# OSIVE_Slim.net
KiCad netlist of a schematic drawn in EAGLE
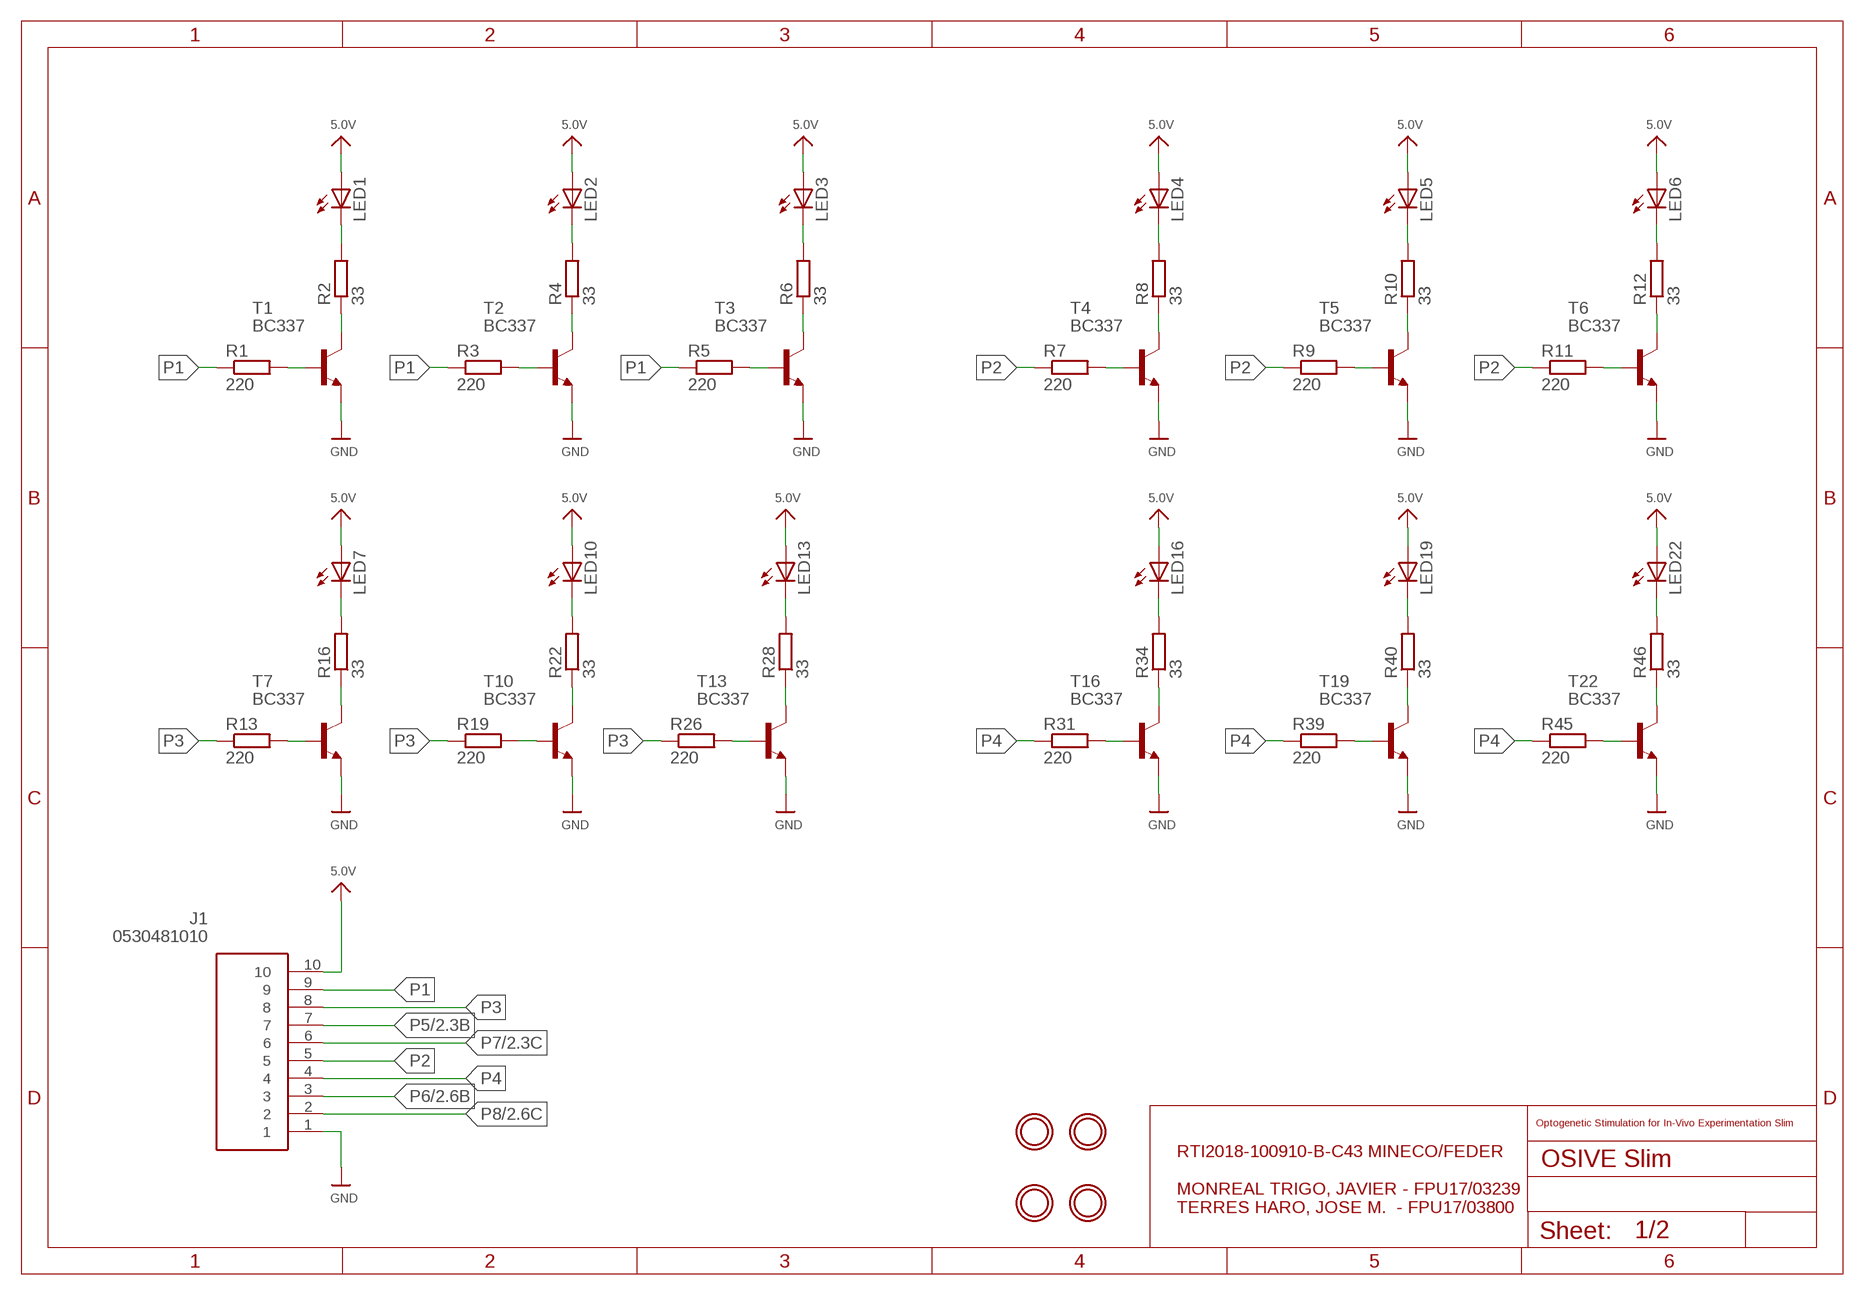
[diagram p0: schematic, sheet 1]
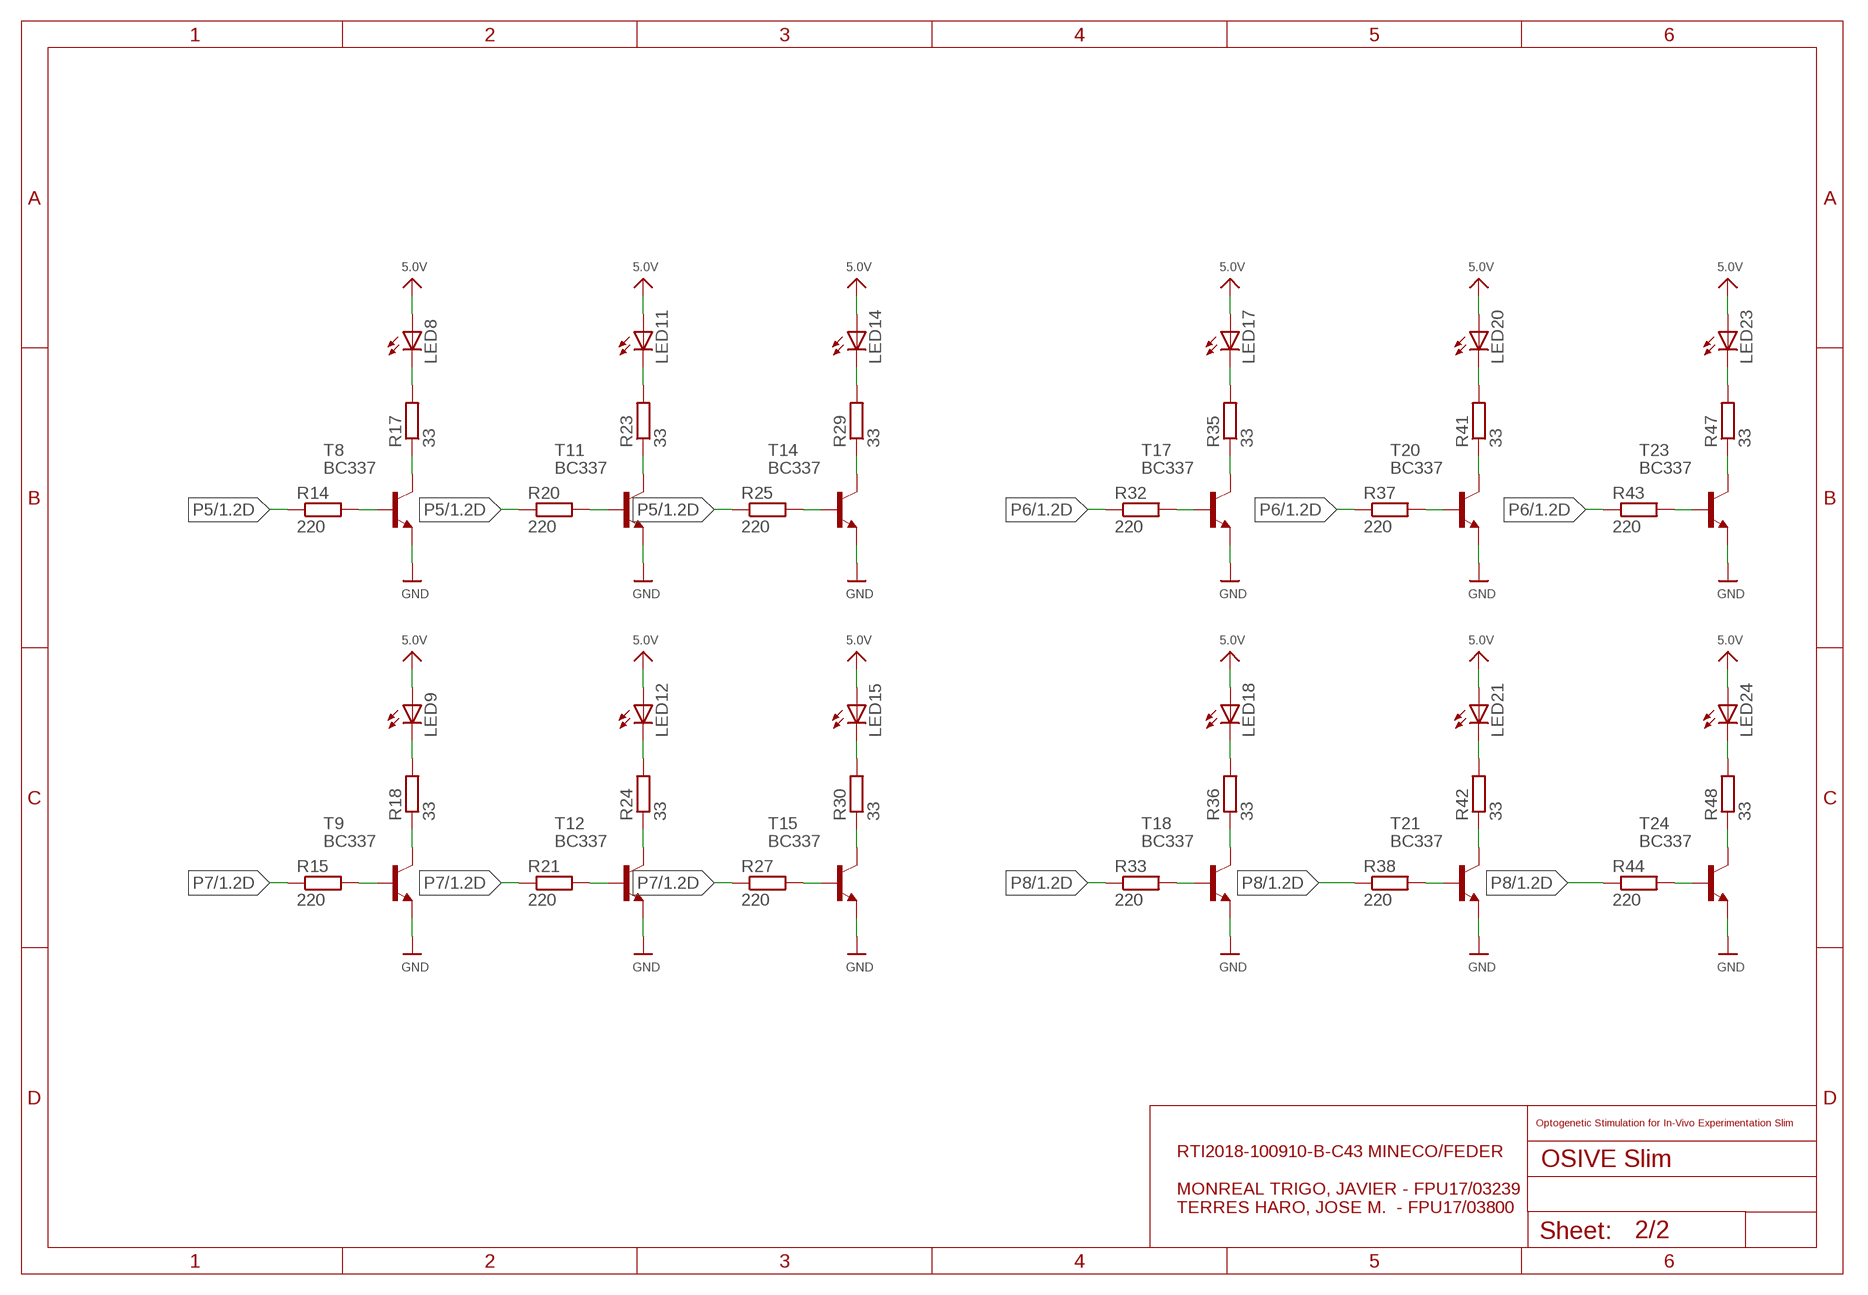
[diagram p1: schematic, sheet 2]

(export (version "E")
  (design (tool "Eeschema 10.0.6"))
  (components
    (comp (ref "LED8")
      (value "LED5MM")
      (footprint "eagle-import:LED5MM")
      (libsource (lib "eagle-import") (part "LED5MM"))
    )
    (comp (ref "LED9")
      (value "LED5MM")
      (footprint "eagle-import:LED5MM")
      (libsource (lib "eagle-import") (part "LED5MM"))
    )
    (comp (ref "LED11")
      (value "LED5MM")
      (footprint "eagle-import:LED5MM")
      (libsource (lib "eagle-import") (part "LED5MM"))
    )
    (comp (ref "LED12")
      (value "LED5MM")
      (footprint "eagle-import:LED5MM")
      (libsource (lib "eagle-import") (part "LED5MM"))
    )
    (comp (ref "LED14")
      (value "LED5MM")
      (footprint "eagle-import:LED5MM")
      (libsource (lib "eagle-import") (part "LED5MM"))
    )
    (comp (ref "LED15")
      (value "LED5MM")
      (footprint "eagle-import:LED5MM")
      (libsource (lib "eagle-import") (part "LED5MM"))
    )
    (comp (ref "LED17")
      (value "LED5MM")
      (footprint "eagle-import:LED5MM")
      (libsource (lib "eagle-import") (part "LED5MM"))
    )
    (comp (ref "LED18")
      (value "LED5MM")
      (footprint "eagle-import:LED5MM")
      (libsource (lib "eagle-import") (part "LED5MM"))
    )
    (comp (ref "LED20")
      (value "LED5MM")
      (footprint "eagle-import:LED5MM")
      (libsource (lib "eagle-import") (part "LED5MM"))
    )
    (comp (ref "LED21")
      (value "LED5MM")
      (footprint "eagle-import:LED5MM")
      (libsource (lib "eagle-import") (part "LED5MM"))
    )
    (comp (ref "LED23")
      (value "LED5MM")
      (footprint "eagle-import:LED5MM")
      (libsource (lib "eagle-import") (part "LED5MM"))
    )
    (comp (ref "LED24")
      (value "LED5MM")
      (footprint "eagle-import:LED5MM")
      (libsource (lib "eagle-import") (part "LED5MM"))
    )
    (comp (ref "R14")
      (value "220")
      (footprint "eagle-import:0204_7")
      (libsource (lib "eagle-import") (part "R-EU_0204/7"))
    )
    (comp (ref "R15")
      (value "220")
      (footprint "eagle-import:0204_7")
      (libsource (lib "eagle-import") (part "R-EU_0204/7"))
    )
    (comp (ref "R17")
      (value "33")
      (footprint "eagle-import:0204_7")
      (libsource (lib "eagle-import") (part "R-EU_0204/7"))
    )
    (comp (ref "R18")
      (value "33")
      (footprint "eagle-import:0204_7")
      (libsource (lib "eagle-import") (part "R-EU_0204/7"))
    )
    (comp (ref "R20")
      (value "220")
      (footprint "eagle-import:0204_7")
      (libsource (lib "eagle-import") (part "R-EU_0204/7"))
    )
    (comp (ref "R21")
      (value "220")
      (footprint "eagle-import:0204_7")
      (libsource (lib "eagle-import") (part "R-EU_0204/7"))
    )
    (comp (ref "R23")
      (value "33")
      (footprint "eagle-import:0204_7")
      (libsource (lib "eagle-import") (part "R-EU_0204/7"))
    )
    (comp (ref "R24")
      (value "33")
      (footprint "eagle-import:0204_7")
      (libsource (lib "eagle-import") (part "R-EU_0204/7"))
    )
    (comp (ref "R25")
      (value "220")
      (footprint "eagle-import:0204_7")
      (libsource (lib "eagle-import") (part "R-EU_0204/7"))
    )
    (comp (ref "R27")
      (value "220")
      (footprint "eagle-import:0204_7")
      (libsource (lib "eagle-import") (part "R-EU_0204/7"))
    )
    (comp (ref "R29")
      (value "33")
      (footprint "eagle-import:0204_7")
      (libsource (lib "eagle-import") (part "R-EU_0204/7"))
    )
    (comp (ref "R30")
      (value "33")
      (footprint "eagle-import:0204_7")
      (libsource (lib "eagle-import") (part "R-EU_0204/7"))
    )
    (comp (ref "R32")
      (value "220")
      (footprint "eagle-import:0204_7")
      (libsource (lib "eagle-import") (part "R-EU_0204/7"))
    )
    (comp (ref "R33")
      (value "220")
      (footprint "eagle-import:0204_7")
      (libsource (lib "eagle-import") (part "R-EU_0204/7"))
    )
    (comp (ref "R35")
      (value "33")
      (footprint "eagle-import:0204_7")
      (libsource (lib "eagle-import") (part "R-EU_0204/7"))
    )
    (comp (ref "R36")
      (value "33")
      (footprint "eagle-import:0204_7")
      (libsource (lib "eagle-import") (part "R-EU_0204/7"))
    )
    (comp (ref "R37")
      (value "220")
      (footprint "eagle-import:0204_7")
      (libsource (lib "eagle-import") (part "R-EU_0204/7"))
    )
    (comp (ref "R38")
      (value "220")
      (footprint "eagle-import:0204_7")
      (libsource (lib "eagle-import") (part "R-EU_0204/7"))
    )
    (comp (ref "R41")
      (value "33")
      (footprint "eagle-import:0204_7")
      (libsource (lib "eagle-import") (part "R-EU_0204/7"))
    )
    (comp (ref "R42")
      (value "33")
      (footprint "eagle-import:0204_7")
      (libsource (lib "eagle-import") (part "R-EU_0204/7"))
    )
    (comp (ref "R43")
      (value "220")
      (footprint "eagle-import:0204_7")
      (libsource (lib "eagle-import") (part "R-EU_0204/7"))
    )
    (comp (ref "R44")
      (value "220")
      (footprint "eagle-import:0204_7")
      (libsource (lib "eagle-import") (part "R-EU_0204/7"))
    )
    (comp (ref "R47")
      (value "33")
      (footprint "eagle-import:0204_7")
      (libsource (lib "eagle-import") (part "R-EU_0204/7"))
    )
    (comp (ref "R48")
      (value "33")
      (footprint "eagle-import:0204_7")
      (libsource (lib "eagle-import") (part "R-EU_0204/7"))
    )
    (comp (ref "T8")
      (value "BC337")
      (footprint "eagle-import:TO92")
      (libsource (lib "eagle-import") (part "BC337"))
    )
    (comp (ref "T9")
      (value "BC337")
      (footprint "eagle-import:TO92")
      (libsource (lib "eagle-import") (part "BC337"))
    )
    (comp (ref "T11")
      (value "BC337")
      (footprint "eagle-import:TO92")
      (libsource (lib "eagle-import") (part "BC337"))
    )
    (comp (ref "T12")
      (value "BC337")
      (footprint "eagle-import:TO92")
      (libsource (lib "eagle-import") (part "BC337"))
    )
    (comp (ref "T14")
      (value "BC337")
      (footprint "eagle-import:TO92")
      (libsource (lib "eagle-import") (part "BC337"))
    )
    (comp (ref "T15")
      (value "BC337")
      (footprint "eagle-import:TO92")
      (libsource (lib "eagle-import") (part "BC337"))
    )
    (comp (ref "T17")
      (value "BC337")
      (footprint "eagle-import:TO92")
      (libsource (lib "eagle-import") (part "BC337"))
    )
    (comp (ref "T18")
      (value "BC337")
      (footprint "eagle-import:TO92")
      (libsource (lib "eagle-import") (part "BC337"))
    )
    (comp (ref "T20")
      (value "BC337")
      (footprint "eagle-import:TO92")
      (libsource (lib "eagle-import") (part "BC337"))
    )
    (comp (ref "T21")
      (value "BC337")
      (footprint "eagle-import:TO92")
      (libsource (lib "eagle-import") (part "BC337"))
    )
    (comp (ref "T23")
      (value "BC337")
      (footprint "eagle-import:TO92")
      (libsource (lib "eagle-import") (part "BC337"))
    )
    (comp (ref "T24")
      (value "BC337")
      (footprint "eagle-import:TO92")
      (libsource (lib "eagle-import") (part "BC337"))
    )
    (comp (ref "H1")
      (value "MOUNTINGHOLE3.0THIN")
      (footprint "eagle-import:MOUNTINGHOLE_3.0_PLATEDTHIN")
      (libsource (lib "eagle-import") (part "MOUNTINGHOLE3.0THIN"))
    )
    (comp (ref "H2")
      (value "MOUNTINGHOLE3.0THIN")
      (footprint "eagle-import:MOUNTINGHOLE_3.0_PLATEDTHIN")
      (libsource (lib "eagle-import") (part "MOUNTINGHOLE3.0THIN"))
    )
    (comp (ref "H3")
      (value "MOUNTINGHOLE3.0THIN")
      (footprint "eagle-import:MOUNTINGHOLE_3.0_PLATEDTHIN")
      (libsource (lib "eagle-import") (part "MOUNTINGHOLE3.0THIN"))
    )
    (comp (ref "H4")
      (value "MOUNTINGHOLE3.0THIN")
      (footprint "eagle-import:MOUNTINGHOLE_3.0_PLATEDTHIN")
      (libsource (lib "eagle-import") (part "MOUNTINGHOLE3.0THIN"))
    )
    (comp (ref "J1")
      (value "0530481010")
      (footprint "eagle-import:0530481010")
      (libsource (lib "eagle-import") (part "0530481010"))
    )
    (comp (ref "LED1")
      (value "LED5MM")
      (footprint "eagle-import:LED5MM")
      (libsource (lib "eagle-import") (part "LED5MM"))
    )
    (comp (ref "LED2")
      (value "LED5MM")
      (footprint "eagle-import:LED5MM")
      (libsource (lib "eagle-import") (part "LED5MM"))
    )
    (comp (ref "LED3")
      (value "LED5MM")
      (footprint "eagle-import:LED5MM")
      (libsource (lib "eagle-import") (part "LED5MM"))
    )
    (comp (ref "LED4")
      (value "LED5MM")
      (footprint "eagle-import:LED5MM")
      (libsource (lib "eagle-import") (part "LED5MM"))
    )
    (comp (ref "LED5")
      (value "LED5MM")
      (footprint "eagle-import:LED5MM")
      (libsource (lib "eagle-import") (part "LED5MM"))
    )
    (comp (ref "LED6")
      (value "LED5MM")
      (footprint "eagle-import:LED5MM")
      (libsource (lib "eagle-import") (part "LED5MM"))
    )
    (comp (ref "LED7")
      (value "LED5MM")
      (footprint "eagle-import:LED5MM")
      (libsource (lib "eagle-import") (part "LED5MM"))
    )
    (comp (ref "LED10")
      (value "LED5MM")
      (footprint "eagle-import:LED5MM")
      (libsource (lib "eagle-import") (part "LED5MM"))
    )
    (comp (ref "LED13")
      (value "LED5MM")
      (footprint "eagle-import:LED5MM")
      (libsource (lib "eagle-import") (part "LED5MM"))
    )
    (comp (ref "LED16")
      (value "LED5MM")
      (footprint "eagle-import:LED5MM")
      (libsource (lib "eagle-import") (part "LED5MM"))
    )
    (comp (ref "LED19")
      (value "LED5MM")
      (footprint "eagle-import:LED5MM")
      (libsource (lib "eagle-import") (part "LED5MM"))
    )
    (comp (ref "LED22")
      (value "LED5MM")
      (footprint "eagle-import:LED5MM")
      (libsource (lib "eagle-import") (part "LED5MM"))
    )
    (comp (ref "R1")
      (value "220")
      (footprint "eagle-import:0204_7")
      (libsource (lib "eagle-import") (part "R-EU_0204/7"))
    )
    (comp (ref "R2")
      (value "33")
      (footprint "eagle-import:0204_7")
      (libsource (lib "eagle-import") (part "R-EU_0204/7"))
    )
    (comp (ref "R3")
      (value "220")
      (footprint "eagle-import:0204_7")
      (libsource (lib "eagle-import") (part "R-EU_0204/7"))
    )
    (comp (ref "R4")
      (value "33")
      (footprint "eagle-import:0204_7")
      (libsource (lib "eagle-import") (part "R-EU_0204/7"))
    )
    (comp (ref "R5")
      (value "220")
      (footprint "eagle-import:0204_7")
      (libsource (lib "eagle-import") (part "R-EU_0204/7"))
    )
    (comp (ref "R6")
      (value "33")
      (footprint "eagle-import:0204_7")
      (libsource (lib "eagle-import") (part "R-EU_0204/7"))
    )
    (comp (ref "R7")
      (value "220")
      (footprint "eagle-import:0204_7")
      (libsource (lib "eagle-import") (part "R-EU_0204/7"))
    )
    (comp (ref "R8")
      (value "33")
      (footprint "eagle-import:0204_7")
      (libsource (lib "eagle-import") (part "R-EU_0204/7"))
    )
    (comp (ref "R9")
      (value "220")
      (footprint "eagle-import:0204_7")
      (libsource (lib "eagle-import") (part "R-EU_0204/7"))
    )
    (comp (ref "R10")
      (value "33")
      (footprint "eagle-import:0204_7")
      (libsource (lib "eagle-import") (part "R-EU_0204/7"))
    )
    (comp (ref "R11")
      (value "220")
      (footprint "eagle-import:0204_7")
      (libsource (lib "eagle-import") (part "R-EU_0204/7"))
    )
    (comp (ref "R12")
      (value "33")
      (footprint "eagle-import:0204_7")
      (libsource (lib "eagle-import") (part "R-EU_0204/7"))
    )
    (comp (ref "R13")
      (value "220")
      (footprint "eagle-import:0204_7")
      (libsource (lib "eagle-import") (part "R-EU_0204/7"))
    )
    (comp (ref "R16")
      (value "33")
      (footprint "eagle-import:0204_7")
      (libsource (lib "eagle-import") (part "R-EU_0204/7"))
    )
    (comp (ref "R19")
      (value "220")
      (footprint "eagle-import:0204_7")
      (libsource (lib "eagle-import") (part "R-EU_0204/7"))
    )
    (comp (ref "R22")
      (value "33")
      (footprint "eagle-import:0204_7")
      (libsource (lib "eagle-import") (part "R-EU_0204/7"))
    )
    (comp (ref "R26")
      (value "220")
      (footprint "eagle-import:0204_7")
      (libsource (lib "eagle-import") (part "R-EU_0204/7"))
    )
    (comp (ref "R28")
      (value "33")
      (footprint "eagle-import:0204_7")
      (libsource (lib "eagle-import") (part "R-EU_0204/7"))
    )
    (comp (ref "R31")
      (value "220")
      (footprint "eagle-import:0204_7")
      (libsource (lib "eagle-import") (part "R-EU_0204/7"))
    )
    (comp (ref "R34")
      (value "33")
      (footprint "eagle-import:0204_7")
      (libsource (lib "eagle-import") (part "R-EU_0204/7"))
    )
    (comp (ref "R39")
      (value "220")
      (footprint "eagle-import:0204_7")
      (libsource (lib "eagle-import") (part "R-EU_0204/7"))
    )
    (comp (ref "R40")
      (value "33")
      (footprint "eagle-import:0204_7")
      (libsource (lib "eagle-import") (part "R-EU_0204/7"))
    )
    (comp (ref "R45")
      (value "220")
      (footprint "eagle-import:0204_7")
      (libsource (lib "eagle-import") (part "R-EU_0204/7"))
    )
    (comp (ref "R46")
      (value "33")
      (footprint "eagle-import:0204_7")
      (libsource (lib "eagle-import") (part "R-EU_0204/7"))
    )
    (comp (ref "T1")
      (value "BC337")
      (footprint "eagle-import:TO92")
      (libsource (lib "eagle-import") (part "BC337"))
    )
    (comp (ref "T2")
      (value "BC337")
      (footprint "eagle-import:TO92")
      (libsource (lib "eagle-import") (part "BC337"))
    )
    (comp (ref "T3")
      (value "BC337")
      (footprint "eagle-import:TO92")
      (libsource (lib "eagle-import") (part "BC337"))
    )
    (comp (ref "T4")
      (value "BC337")
      (footprint "eagle-import:TO92")
      (libsource (lib "eagle-import") (part "BC337"))
    )
    (comp (ref "T5")
      (value "BC337")
      (footprint "eagle-import:TO92")
      (libsource (lib "eagle-import") (part "BC337"))
    )
    (comp (ref "T6")
      (value "BC337")
      (footprint "eagle-import:TO92")
      (libsource (lib "eagle-import") (part "BC337"))
    )
    (comp (ref "T7")
      (value "BC337")
      (footprint "eagle-import:TO92")
      (libsource (lib "eagle-import") (part "BC337"))
    )
    (comp (ref "T10")
      (value "BC337")
      (footprint "eagle-import:TO92")
      (libsource (lib "eagle-import") (part "BC337"))
    )
    (comp (ref "T13")
      (value "BC337")
      (footprint "eagle-import:TO92")
      (libsource (lib "eagle-import") (part "BC337"))
    )
    (comp (ref "T16")
      (value "BC337")
      (footprint "eagle-import:TO92")
      (libsource (lib "eagle-import") (part "BC337"))
    )
    (comp (ref "T19")
      (value "BC337")
      (footprint "eagle-import:TO92")
      (libsource (lib "eagle-import") (part "BC337"))
    )
    (comp (ref "T22")
      (value "BC337")
      (footprint "eagle-import:TO92")
      (libsource (lib "eagle-import") (part "BC337"))
    )
  )
  (nets
    (net (code "1") (name "5.0V") (class "Default")
      (node (ref "J1") (pin "10") (pinfunction "10_10") (pintype "bidirectional"))
      (node (ref "LED1") (pin "A") (pinfunction "A_A") (pintype "passive"))
      (node (ref "LED10") (pin "A") (pinfunction "A_A") (pintype "passive"))
      (node (ref "LED11") (pin "A") (pinfunction "A_A") (pintype "passive"))
      (node (ref "LED12") (pin "A") (pinfunction "A_A") (pintype "passive"))
      (node (ref "LED13") (pin "A") (pinfunction "A_A") (pintype "passive"))
      (node (ref "LED14") (pin "A") (pinfunction "A_A") (pintype "passive"))
      (node (ref "LED15") (pin "A") (pinfunction "A_A") (pintype "passive"))
      (node (ref "LED16") (pin "A") (pinfunction "A_A") (pintype "passive"))
      (node (ref "LED17") (pin "A") (pinfunction "A_A") (pintype "passive"))
      (node (ref "LED18") (pin "A") (pinfunction "A_A") (pintype "passive"))
      (node (ref "LED19") (pin "A") (pinfunction "A_A") (pintype "passive"))
      (node (ref "LED2") (pin "A") (pinfunction "A_A") (pintype "passive"))
      (node (ref "LED20") (pin "A") (pinfunction "A_A") (pintype "passive"))
      (node (ref "LED21") (pin "A") (pinfunction "A_A") (pintype "passive"))
      (node (ref "LED22") (pin "A") (pinfunction "A_A") (pintype "passive"))
      (node (ref "LED23") (pin "A") (pinfunction "A_A") (pintype "passive"))
      (node (ref "LED24") (pin "A") (pinfunction "A_A") (pintype "passive"))
      (node (ref "LED3") (pin "A") (pinfunction "A_A") (pintype "passive"))
      (node (ref "LED4") (pin "A") (pinfunction "A_A") (pintype "passive"))
      (node (ref "LED5") (pin "A") (pinfunction "A_A") (pintype "passive"))
      (node (ref "LED6") (pin "A") (pinfunction "A_A") (pintype "passive"))
      (node (ref "LED7") (pin "A") (pinfunction "A_A") (pintype "passive"))
      (node (ref "LED8") (pin "A") (pinfunction "A_A") (pintype "passive"))
      (node (ref "LED9") (pin "A") (pinfunction "A_A") (pintype "passive"))
    )
    (net (code "2") (name "GND") (class "Default")
      (node (ref "J1") (pin "1") (pinfunction "1_1") (pintype "bidirectional"))
      (node (ref "T1") (pin "1") (pinfunction "E_1") (pintype "passive"))
      (node (ref "T10") (pin "1") (pinfunction "E_1") (pintype "passive"))
      (node (ref "T11") (pin "1") (pinfunction "E_1") (pintype "passive"))
      (node (ref "T12") (pin "1") (pinfunction "E_1") (pintype "passive"))
      (node (ref "T13") (pin "1") (pinfunction "E_1") (pintype "passive"))
      (node (ref "T14") (pin "1") (pinfunction "E_1") (pintype "passive"))
      (node (ref "T15") (pin "1") (pinfunction "E_1") (pintype "passive"))
      (node (ref "T16") (pin "1") (pinfunction "E_1") (pintype "passive"))
      (node (ref "T17") (pin "1") (pinfunction "E_1") (pintype "passive"))
      (node (ref "T18") (pin "1") (pinfunction "E_1") (pintype "passive"))
      (node (ref "T19") (pin "1") (pinfunction "E_1") (pintype "passive"))
      (node (ref "T2") (pin "1") (pinfunction "E_1") (pintype "passive"))
      (node (ref "T20") (pin "1") (pinfunction "E_1") (pintype "passive"))
      (node (ref "T21") (pin "1") (pinfunction "E_1") (pintype "passive"))
      (node (ref "T22") (pin "1") (pinfunction "E_1") (pintype "passive"))
      (node (ref "T23") (pin "1") (pinfunction "E_1") (pintype "passive"))
      (node (ref "T24") (pin "1") (pinfunction "E_1") (pintype "passive"))
      (node (ref "T3") (pin "1") (pinfunction "E_1") (pintype "passive"))
      (node (ref "T4") (pin "1") (pinfunction "E_1") (pintype "passive"))
      (node (ref "T5") (pin "1") (pinfunction "E_1") (pintype "passive"))
      (node (ref "T6") (pin "1") (pinfunction "E_1") (pintype "passive"))
      (node (ref "T7") (pin "1") (pinfunction "E_1") (pintype "passive"))
      (node (ref "T8") (pin "1") (pinfunction "E_1") (pintype "passive"))
      (node (ref "T9") (pin "1") (pinfunction "E_1") (pintype "passive"))
    )
    (net (code "3") (name "Net-(LED1-C)") (class "Default")
      (node (ref "LED1") (pin "K") (pinfunction "C_K") (pintype "passive"))
      (node (ref "R2") (pin "2") (pinfunction "2_2") (pintype "passive"))
    )
    (net (code "4") (name "Net-(LED2-C)") (class "Default")
      (node (ref "LED2") (pin "K") (pinfunction "C_K") (pintype "passive"))
      (node (ref "R4") (pin "2") (pinfunction "2_2") (pintype "passive"))
    )
    (net (code "5") (name "Net-(LED3-C)") (class "Default")
      (node (ref "LED3") (pin "K") (pinfunction "C_K") (pintype "passive"))
      (node (ref "R6") (pin "2") (pinfunction "2_2") (pintype "passive"))
    )
    (net (code "6") (name "Net-(LED4-C)") (class "Default")
      (node (ref "LED4") (pin "K") (pinfunction "C_K") (pintype "passive"))
      (node (ref "R8") (pin "2") (pinfunction "2_2") (pintype "passive"))
    )
    (net (code "7") (name "Net-(LED5-C)") (class "Default")
      (node (ref "LED5") (pin "K") (pinfunction "C_K") (pintype "passive"))
      (node (ref "R10") (pin "2") (pinfunction "2_2") (pintype "passive"))
    )
    (net (code "8") (name "Net-(LED6-C)") (class "Default")
      (node (ref "LED6") (pin "K") (pinfunction "C_K") (pintype "passive"))
      (node (ref "R12") (pin "2") (pinfunction "2_2") (pintype "passive"))
    )
    (net (code "9") (name "Net-(LED7-C)") (class "Default")
      (node (ref "LED7") (pin "K") (pinfunction "C_K") (pintype "passive"))
      (node (ref "R16") (pin "2") (pinfunction "2_2") (pintype "passive"))
    )
    (net (code "10") (name "Net-(LED8-C)") (class "Default")
      (node (ref "LED8") (pin "K") (pinfunction "C_K") (pintype "passive"))
      (node (ref "R17") (pin "2") (pinfunction "2_2") (pintype "passive"))
    )
    (net (code "11") (name "Net-(LED9-C)") (class "Default")
      (node (ref "LED9") (pin "K") (pinfunction "C_K") (pintype "passive"))
      (node (ref "R18") (pin "2") (pinfunction "2_2") (pintype "passive"))
    )
    (net (code "12") (name "Net-(LED10-C)") (class "Default")
      (node (ref "LED10") (pin "K") (pinfunction "C_K") (pintype "passive"))
      (node (ref "R22") (pin "2") (pinfunction "2_2") (pintype "passive"))
    )
    (net (code "13") (name "Net-(LED11-C)") (class "Default")
      (node (ref "LED11") (pin "K") (pinfunction "C_K") (pintype "passive"))
      (node (ref "R23") (pin "2") (pinfunction "2_2") (pintype "passive"))
    )
    (net (code "14") (name "Net-(LED12-C)") (class "Default")
      (node (ref "LED12") (pin "K") (pinfunction "C_K") (pintype "passive"))
      (node (ref "R24") (pin "2") (pinfunction "2_2") (pintype "passive"))
    )
    (net (code "15") (name "Net-(LED13-C)") (class "Default")
      (node (ref "LED13") (pin "K") (pinfunction "C_K") (pintype "passive"))
      (node (ref "R28") (pin "2") (pinfunction "2_2") (pintype "passive"))
    )
    (net (code "16") (name "Net-(LED14-C)") (class "Default")
      (node (ref "LED14") (pin "K") (pinfunction "C_K") (pintype "passive"))
      (node (ref "R29") (pin "2") (pinfunction "2_2") (pintype "passive"))
    )
    (net (code "17") (name "Net-(LED15-C)") (class "Default")
      (node (ref "LED15") (pin "K") (pinfunction "C_K") (pintype "passive"))
      (node (ref "R30") (pin "2") (pinfunction "2_2") (pintype "passive"))
    )
    (net (code "18") (name "Net-(LED16-C)") (class "Default")
      (node (ref "LED16") (pin "K") (pinfunction "C_K") (pintype "passive"))
      (node (ref "R34") (pin "2") (pinfunction "2_2") (pintype "passive"))
    )
    (net (code "19") (name "Net-(LED17-C)") (class "Default")
      (node (ref "LED17") (pin "K") (pinfunction "C_K") (pintype "passive"))
      (node (ref "R35") (pin "2") (pinfunction "2_2") (pintype "passive"))
    )
    (net (code "20") (name "Net-(LED18-C)") (class "Default")
      (node (ref "LED18") (pin "K") (pinfunction "C_K") (pintype "passive"))
      (node (ref "R36") (pin "2") (pinfunction "2_2") (pintype "passive"))
    )
    (net (code "21") (name "Net-(LED19-C)") (class "Default")
      (node (ref "LED19") (pin "K") (pinfunction "C_K") (pintype "passive"))
      (node (ref "R40") (pin "2") (pinfunction "2_2") (pintype "passive"))
    )
    (net (code "22") (name "Net-(LED20-C)") (class "Default")
      (node (ref "LED20") (pin "K") (pinfunction "C_K") (pintype "passive"))
      (node (ref "R41") (pin "2") (pinfunction "2_2") (pintype "passive"))
    )
    (net (code "23") (name "Net-(LED21-C)") (class "Default")
      (node (ref "LED21") (pin "K") (pinfunction "C_K") (pintype "passive"))
      (node (ref "R42") (pin "2") (pinfunction "2_2") (pintype "passive"))
    )
    (net (code "24") (name "Net-(LED22-C)") (class "Default")
      (node (ref "LED22") (pin "K") (pinfunction "C_K") (pintype "passive"))
      (node (ref "R46") (pin "2") (pinfunction "2_2") (pintype "passive"))
    )
    (net (code "25") (name "Net-(LED23-C)") (class "Default")
      (node (ref "LED23") (pin "K") (pinfunction "C_K") (pintype "passive"))
      (node (ref "R47") (pin "2") (pinfunction "2_2") (pintype "passive"))
    )
    (net (code "26") (name "Net-(LED24-C)") (class "Default")
      (node (ref "LED24") (pin "K") (pinfunction "C_K") (pintype "passive"))
      (node (ref "R48") (pin "2") (pinfunction "2_2") (pintype "passive"))
    )
    (net (code "27") (name "Net-(T1-B)") (class "Default")
      (node (ref "R1") (pin "2") (pinfunction "2_2") (pintype "passive"))
      (node (ref "T1") (pin "2") (pinfunction "B_2") (pintype "passive"))
    )
    (net (code "28") (name "Net-(T1-C)") (class "Default")
      (node (ref "R2") (pin "1") (pinfunction "1_1") (pintype "passive"))
      (node (ref "T1") (pin "3") (pinfunction "C_3") (pintype "passive"))
    )
    (net (code "29") (name "Net-(T2-B)") (class "Default")
      (node (ref "R3") (pin "2") (pinfunction "2_2") (pintype "passive"))
      (node (ref "T2") (pin "2") (pinfunction "B_2") (pintype "passive"))
    )
    (net (code "30") (name "Net-(T2-C)") (class "Default")
      (node (ref "R4") (pin "1") (pinfunction "1_1") (pintype "passive"))
      (node (ref "T2") (pin "3") (pinfunction "C_3") (pintype "passive"))
    )
    (net (code "31") (name "Net-(T3-B)") (class "Default")
      (node (ref "R5") (pin "2") (pinfunction "2_2") (pintype "passive"))
      (node (ref "T3") (pin "2") (pinfunction "B_2") (pintype "passive"))
    )
    (net (code "32") (name "Net-(T3-C)") (class "Default")
      (node (ref "R6") (pin "1") (pinfunction "1_1") (pintype "passive"))
      (node (ref "T3") (pin "3") (pinfunction "C_3") (pintype "passive"))
    )
    (net (code "33") (name "Net-(T4-B)") (class "Default")
      (node (ref "R7") (pin "2") (pinfunction "2_2") (pintype "passive"))
      (node (ref "T4") (pin "2") (pinfunction "B_2") (pintype "passive"))
    )
    (net (code "34") (name "Net-(T4-C)") (class "Default")
      (node (ref "R8") (pin "1") (pinfunction "1_1") (pintype "passive"))
      (node (ref "T4") (pin "3") (pinfunction "C_3") (pintype "passive"))
    )
    (net (code "35") (name "Net-(T5-B)") (class "Default")
      (node (ref "R9") (pin "2") (pinfunction "2_2") (pintype "passive"))
      (node (ref "T5") (pin "2") (pinfunction "B_2") (pintype "passive"))
    )
    (net (code "36") (name "Net-(T5-C)") (class "Default")
      (node (ref "R10") (pin "1") (pinfunction "1_1") (pintype "passive"))
      (node (ref "T5") (pin "3") (pinfunction "C_3") (pintype "passive"))
    )
    (net (code "37") (name "Net-(T6-B)") (class "Default")
      (node (ref "R11") (pin "2") (pinfunction "2_2") (pintype "passive"))
      (node (ref "T6") (pin "2") (pinfunction "B_2") (pintype "passive"))
    )
    (net (code "38") (name "Net-(T6-C)") (class "Default")
      (node (ref "R12") (pin "1") (pinfunction "1_1") (pintype "passive"))
      (node (ref "T6") (pin "3") (pinfunction "C_3") (pintype "passive"))
    )
    (net (code "39") (name "Net-(T7-B)") (class "Default")
      (node (ref "R13") (pin "2") (pinfunction "2_2") (pintype "passive"))
      (node (ref "T7") (pin "2") (pinfunction "B_2") (pintype "passive"))
    )
    (net (code "40") (name "Net-(T7-C)") (class "Default")
      (node (ref "R16") (pin "1") (pinfunction "1_1") (pintype "passive"))
      (node (ref "T7") (pin "3") (pinfunction "C_3") (pintype "passive"))
    )
    (net (code "41") (name "Net-(T8-B)") (class "Default")
      (node (ref "R14") (pin "2") (pinfunction "2_2") (pintype "passive"))
      (node (ref "T8") (pin "2") (pinfunction "B_2") (pintype "passive"))
    )
    (net (code "42") (name "Net-(T8-C)") (class "Default")
      (node (ref "R17") (pin "1") (pinfunction "1_1") (pintype "passive"))
      (node (ref "T8") (pin "3") (pinfunction "C_3") (pintype "passive"))
    )
    (net (code "43") (name "Net-(T9-B)") (class "Default")
      (node (ref "R15") (pin "2") (pinfunction "2_2") (pintype "passive"))
      (node (ref "T9") (pin "2") (pinfunction "B_2") (pintype "passive"))
    )
    (net (code "44") (name "Net-(T9-C)") (class "Default")
      (node (ref "R18") (pin "1") (pinfunction "1_1") (pintype "passive"))
      (node (ref "T9") (pin "3") (pinfunction "C_3") (pintype "passive"))
    )
    (net (code "45") (name "Net-(T10-B)") (class "Default")
      (node (ref "R19") (pin "2") (pinfunction "2_2") (pintype "passive"))
      (node (ref "T10") (pin "2") (pinfunction "B_2") (pintype "passive"))
    )
    (net (code "46") (name "Net-(T10-C)") (class "Default")
      (node (ref "R22") (pin "1") (pinfunction "1_1") (pintype "passive"))
      (node (ref "T10") (pin "3") (pinfunction "C_3") (pintype "passive"))
    )
    (net (code "47") (name "Net-(T11-B)") (class "Default")
      (node (ref "R20") (pin "2") (pinfunction "2_2") (pintype "passive"))
      (node (ref "T11") (pin "2") (pinfunction "B_2") (pintype "passive"))
    )
    (net (code "48") (name "Net-(T11-C)") (class "Default")
      (node (ref "R23") (pin "1") (pinfunction "1_1") (pintype "passive"))
      (node (ref "T11") (pin "3") (pinfunction "C_3") (pintype "passive"))
    )
    (net (code "49") (name "Net-(T12-B)") (class "Default")
      (node (ref "R21") (pin "2") (pinfunction "2_2") (pintype "passive"))
      (node (ref "T12") (pin "2") (pinfunction "B_2") (pintype "passive"))
    )
    (net (code "50") (name "Net-(T12-C)") (class "Default")
      (node (ref "R24") (pin "1") (pinfunction "1_1") (pintype "passive"))
      (node (ref "T12") (pin "3") (pinfunction "C_3") (pintype "passive"))
    )
    (net (code "51") (name "Net-(T13-B)") (class "Default")
      (node (ref "R26") (pin "2") (pinfunction "2_2") (pintype "passive"))
      (node (ref "T13") (pin "2") (pinfunction "B_2") (pintype "passive"))
    )
    (net (code "52") (name "Net-(T13-C)") (class "Default")
      (node (ref "R28") (pin "1") (pinfunction "1_1") (pintype "passive"))
      (node (ref "T13") (pin "3") (pinfunction "C_3") (pintype "passive"))
    )
    (net (code "53") (name "Net-(T14-B)") (class "Default")
      (node (ref "R25") (pin "2") (pinfunction "2_2") (pintype "passive"))
      (node (ref "T14") (pin "2") (pinfunction "B_2") (pintype "passive"))
    )
    (net (code "54") (name "Net-(T14-C)") (class "Default")
      (node (ref "R29") (pin "1") (pinfunction "1_1") (pintype "passive"))
      (node (ref "T14") (pin "3") (pinfunction "C_3") (pintype "passive"))
    )
    (net (code "55") (name "Net-(T15-B)") (class "Default")
      (node (ref "R27") (pin "2") (pinfunction "2_2") (pintype "passive"))
      (node (ref "T15") (pin "2") (pinfunction "B_2") (pintype "passive"))
    )
    (net (code "56") (name "Net-(T15-C)") (class "Default")
      (node (ref "R30") (pin "1") (pinfunction "1_1") (pintype "passive"))
      (node (ref "T15") (pin "3") (pinfunction "C_3") (pintype "passive"))
    )
    (net (code "57") (name "Net-(T16-B)") (class "Default")
      (node (ref "R31") (pin "2") (pinfunction "2_2") (pintype "passive"))
      (node (ref "T16") (pin "2") (pinfunction "B_2") (pintype "passive"))
    )
    (net (code "58") (name "Net-(T16-C)") (class "Default")
      (node (ref "R34") (pin "1") (pinfunction "1_1") (pintype "passive"))
      (node (ref "T16") (pin "3") (pinfunction "C_3") (pintype "passive"))
    )
    (net (code "59") (name "Net-(T17-B)") (class "Default")
      (node (ref "R32") (pin "2") (pinfunction "2_2") (pintype "passive"))
      (node (ref "T17") (pin "2") (pinfunction "B_2") (pintype "passive"))
    )
    (net (code "60") (name "Net-(T17-C)") (class "Default")
      (node (ref "R35") (pin "1") (pinfunction "1_1") (pintype "passive"))
      (node (ref "T17") (pin "3") (pinfunction "C_3") (pintype "passive"))
    )
    (net (code "61") (name "Net-(T18-B)") (class "Default")
      (node (ref "R33") (pin "2") (pinfunction "2_2") (pintype "passive"))
      (node (ref "T18") (pin "2") (pinfunction "B_2") (pintype "passive"))
    )
    (net (code "62") (name "Net-(T18-C)") (class "Default")
      (node (ref "R36") (pin "1") (pinfunction "1_1") (pintype "passive"))
      (node (ref "T18") (pin "3") (pinfunction "C_3") (pintype "passive"))
    )
    (net (code "63") (name "Net-(T19-B)") (class "Default")
      (node (ref "R39") (pin "2") (pinfunction "2_2") (pintype "passive"))
      (node (ref "T19") (pin "2") (pinfunction "B_2") (pintype "passive"))
    )
    (net (code "64") (name "Net-(T19-C)") (class "Default")
      (node (ref "R40") (pin "1") (pinfunction "1_1") (pintype "passive"))
      (node (ref "T19") (pin "3") (pinfunction "C_3") (pintype "passive"))
    )
    (net (code "65") (name "Net-(T20-B)") (class "Default")
      (node (ref "R37") (pin "2") (pinfunction "2_2") (pintype "passive"))
      (node (ref "T20") (pin "2") (pinfunction "B_2") (pintype "passive"))
    )
    (net (code "66") (name "Net-(T20-C)") (class "Default")
      (node (ref "R41") (pin "1") (pinfunction "1_1") (pintype "passive"))
      (node (ref "T20") (pin "3") (pinfunction "C_3") (pintype "passive"))
    )
    (net (code "67") (name "Net-(T21-B)") (class "Default")
      (node (ref "R38") (pin "2") (pinfunction "2_2") (pintype "passive"))
      (node (ref "T21") (pin "2") (pinfunction "B_2") (pintype "passive"))
    )
    (net (code "68") (name "Net-(T21-C)") (class "Default")
      (node (ref "R42") (pin "1") (pinfunction "1_1") (pintype "passive"))
      (node (ref "T21") (pin "3") (pinfunction "C_3") (pintype "passive"))
    )
    (net (code "69") (name "Net-(T22-B)") (class "Default")
      (node (ref "R45") (pin "2") (pinfunction "2_2") (pintype "passive"))
      (node (ref "T22") (pin "2") (pinfunction "B_2") (pintype "passive"))
    )
    (net (code "70") (name "Net-(T22-C)") (class "Default")
      (node (ref "R46") (pin "1") (pinfunction "1_1") (pintype "passive"))
      (node (ref "T22") (pin "3") (pinfunction "C_3") (pintype "passive"))
    )
    (net (code "71") (name "Net-(T23-B)") (class "Default")
      (node (ref "R43") (pin "2") (pinfunction "2_2") (pintype "passive"))
      (node (ref "T23") (pin "2") (pinfunction "B_2") (pintype "passive"))
    )
    (net (code "72") (name "Net-(T23-C)") (class "Default")
      (node (ref "R47") (pin "1") (pinfunction "1_1") (pintype "passive"))
      (node (ref "T23") (pin "3") (pinfunction "C_3") (pintype "passive"))
    )
    (net (code "73") (name "Net-(T24-B)") (class "Default")
      (node (ref "R44") (pin "2") (pinfunction "2_2") (pintype "passive"))
      (node (ref "T24") (pin "2") (pinfunction "B_2") (pintype "passive"))
    )
    (net (code "74") (name "Net-(T24-C)") (class "Default")
      (node (ref "R48") (pin "1") (pinfunction "1_1") (pintype "passive"))
      (node (ref "T24") (pin "3") (pinfunction "C_3") (pintype "passive"))
    )
    (net (code "75") (name "P1") (class "Default")
      (node (ref "J1") (pin "9") (pinfunction "9_9") (pintype "bidirectional"))
      (node (ref "R1") (pin "1") (pinfunction "1_1") (pintype "passive"))
      (node (ref "R3") (pin "1") (pinfunction "1_1") (pintype "passive"))
      (node (ref "R5") (pin "1") (pinfunction "1_1") (pintype "passive"))
    )
    (net (code "76") (name "P2") (class "Default")
      (node (ref "J1") (pin "5") (pinfunction "5_5") (pintype "bidirectional"))
      (node (ref "R11") (pin "1") (pinfunction "1_1") (pintype "passive"))
      (node (ref "R7") (pin "1") (pinfunction "1_1") (pintype "passive"))
      (node (ref "R9") (pin "1") (pinfunction "1_1") (pintype "passive"))
    )
    (net (code "77") (name "P3") (class "Default")
      (node (ref "J1") (pin "8") (pinfunction "8_8") (pintype "bidirectional"))
      (node (ref "R13") (pin "1") (pinfunction "1_1") (pintype "passive"))
      (node (ref "R19") (pin "1") (pinfunction "1_1") (pintype "passive"))
      (node (ref "R26") (pin "1") (pinfunction "1_1") (pintype "passive"))
    )
    (net (code "78") (name "P4") (class "Default")
      (node (ref "J1") (pin "4") (pinfunction "4_4") (pintype "bidirectional"))
      (node (ref "R31") (pin "1") (pinfunction "1_1") (pintype "passive"))
      (node (ref "R39") (pin "1") (pinfunction "1_1") (pintype "passive"))
      (node (ref "R45") (pin "1") (pinfunction "1_1") (pintype "passive"))
    )
    (net (code "79") (name "P5") (class "Default")
      (node (ref "J1") (pin "7") (pinfunction "7_7") (pintype "bidirectional"))
      (node (ref "R14") (pin "1") (pinfunction "1_1") (pintype "passive"))
      (node (ref "R20") (pin "1") (pinfunction "1_1") (pintype "passive"))
      (node (ref "R25") (pin "1") (pinfunction "1_1") (pintype "passive"))
    )
    (net (code "80") (name "P6") (class "Default")
      (node (ref "J1") (pin "3") (pinfunction "3_3") (pintype "bidirectional"))
      (node (ref "R32") (pin "1") (pinfunction "1_1") (pintype "passive"))
      (node (ref "R37") (pin "1") (pinfunction "1_1") (pintype "passive"))
      (node (ref "R43") (pin "1") (pinfunction "1_1") (pintype "passive"))
    )
    (net (code "81") (name "P7") (class "Default")
      (node (ref "J1") (pin "6") (pinfunction "6_6") (pintype "bidirectional"))
      (node (ref "R15") (pin "1") (pinfunction "1_1") (pintype "passive"))
      (node (ref "R21") (pin "1") (pinfunction "1_1") (pintype "passive"))
      (node (ref "R27") (pin "1") (pinfunction "1_1") (pintype "passive"))
    )
    (net (code "82") (name "P8") (class "Default")
      (node (ref "J1") (pin "2") (pinfunction "2_2") (pintype "bidirectional"))
      (node (ref "R33") (pin "1") (pinfunction "1_1") (pintype "passive"))
      (node (ref "R38") (pin "1") (pinfunction "1_1") (pintype "passive"))
      (node (ref "R44") (pin "1") (pinfunction "1_1") (pintype "passive"))
    )
  )
)
